# knobhead.net
KiCad netlist of a schematic drawn in EAGLE
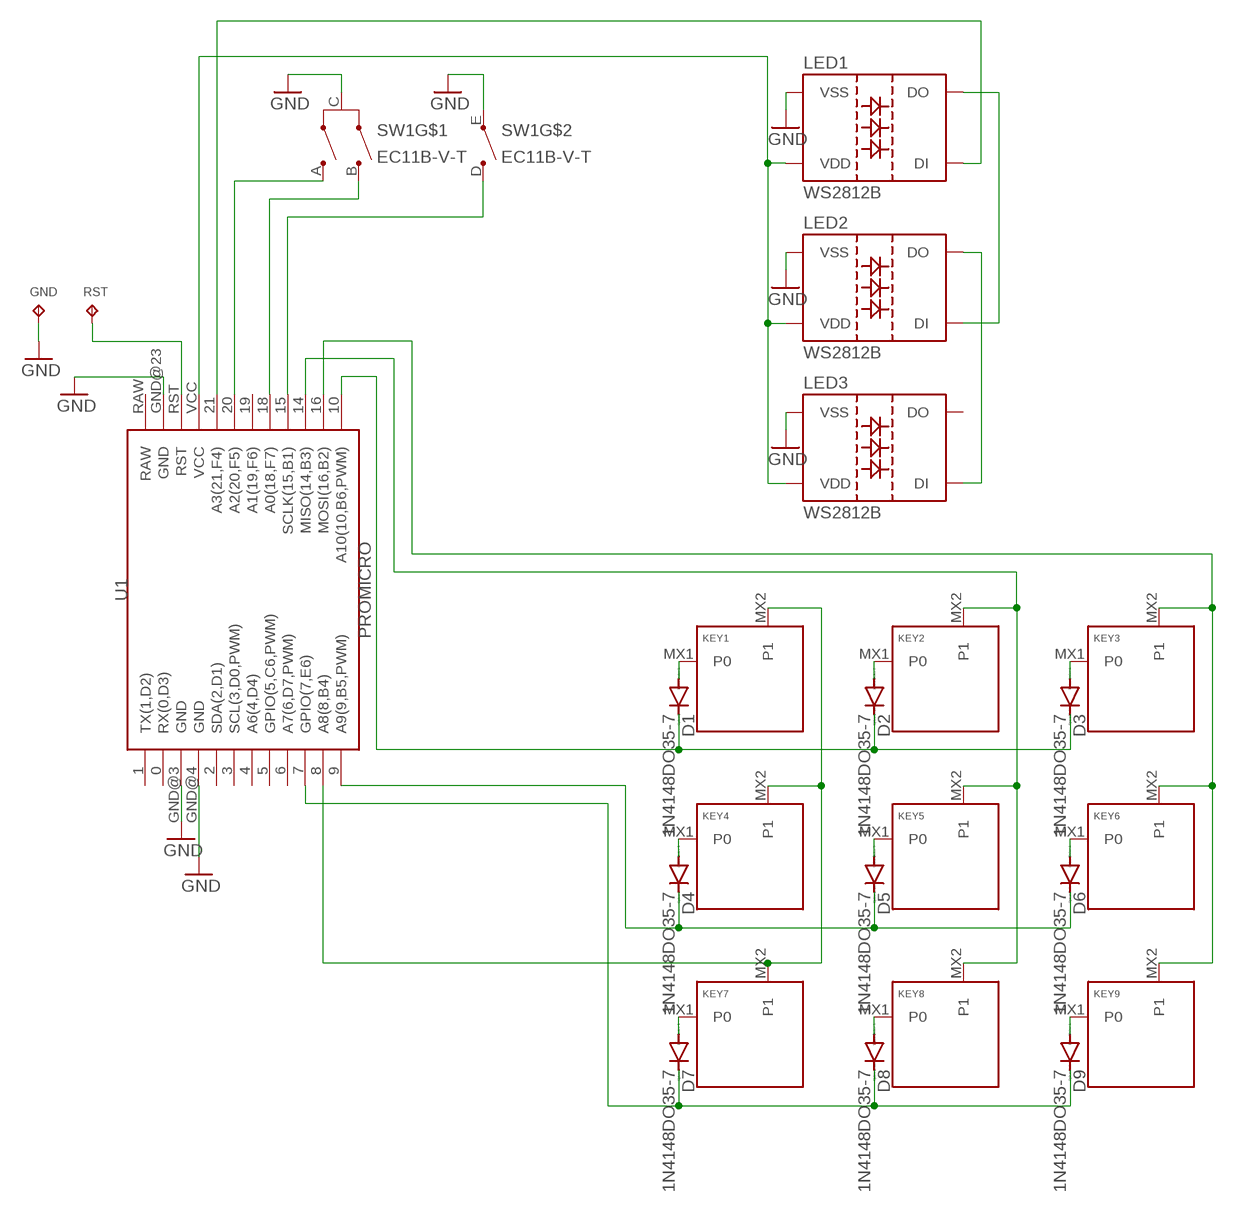
[diagram p0: schematic, sheet 1]

(export (version "E")
  (design (tool "Eeschema 10.0.6"))
  (components
    (comp (ref "D1")
      (value "1N4148DO35-7")
      (footprint "eagle-import:DO35-7")
      (libsource (lib "eagle-import") (part "1N4148DO35-7"))
    )
    (comp (ref "D2")
      (value "1N4148DO35-7")
      (footprint "eagle-import:DO35-7")
      (libsource (lib "eagle-import") (part "1N4148DO35-7"))
    )
    (comp (ref "D3")
      (value "1N4148DO35-7")
      (footprint "eagle-import:DO35-7")
      (libsource (lib "eagle-import") (part "1N4148DO35-7"))
    )
    (comp (ref "D4")
      (value "1N4148DO35-7")
      (footprint "eagle-import:DO35-7")
      (libsource (lib "eagle-import") (part "1N4148DO35-7"))
    )
    (comp (ref "D5")
      (value "1N4148DO35-7")
      (footprint "eagle-import:DO35-7")
      (libsource (lib "eagle-import") (part "1N4148DO35-7"))
    )
    (comp (ref "D6")
      (value "1N4148DO35-7")
      (footprint "eagle-import:DO35-7")
      (libsource (lib "eagle-import") (part "1N4148DO35-7"))
    )
    (comp (ref "D7")
      (value "1N4148DO35-7")
      (footprint "eagle-import:DO35-7")
      (libsource (lib "eagle-import") (part "1N4148DO35-7"))
    )
    (comp (ref "D8")
      (value "1N4148DO35-7")
      (footprint "eagle-import:DO35-7")
      (libsource (lib "eagle-import") (part "1N4148DO35-7"))
    )
    (comp (ref "D9")
      (value "1N4148DO35-7")
      (footprint "eagle-import:DO35-7")
      (libsource (lib "eagle-import") (part "1N4148DO35-7"))
    )
    (comp (ref "GND")
      (value "TPB1,27")
      (footprint "eagle-import:B1,27")
      (libsource (lib "eagle-import") (part "TPB1,27"))
    )
    (comp (ref "KEY1")
      (value "KEYSWITCH-PLAIN-MXHSPCB-1U")
      (footprint "eagle-import:MXHSPCB-1U")
      (libsource (lib "eagle-import") (part "KEYSWITCH-PLAIN-MXHSPCB-1U"))
    )
    (comp (ref "KEY2")
      (value "KEYSWITCH-PLAIN-MXHSPCB-1U")
      (footprint "eagle-import:MXHSPCB-1U")
      (libsource (lib "eagle-import") (part "KEYSWITCH-PLAIN-MXHSPCB-1U"))
    )
    (comp (ref "KEY3")
      (value "KEYSWITCH-PLAIN-MXHSPCB-1U")
      (footprint "eagle-import:MXHSPCB-1U")
      (libsource (lib "eagle-import") (part "KEYSWITCH-PLAIN-MXHSPCB-1U"))
    )
    (comp (ref "KEY4")
      (value "KEYSWITCH-PLAIN-MXHSPCB-1U")
      (footprint "eagle-import:MXHSPCB-1U")
      (libsource (lib "eagle-import") (part "KEYSWITCH-PLAIN-MXHSPCB-1U"))
    )
    (comp (ref "KEY5")
      (value "KEYSWITCH-PLAIN-MXHSPCB-1U")
      (footprint "eagle-import:MXHSPCB-1U")
      (libsource (lib "eagle-import") (part "KEYSWITCH-PLAIN-MXHSPCB-1U"))
    )
    (comp (ref "KEY6")
      (value "KEYSWITCH-PLAIN-MXHSPCB-1U")
      (footprint "eagle-import:MXHSPCB-1U")
      (libsource (lib "eagle-import") (part "KEYSWITCH-PLAIN-MXHSPCB-1U"))
    )
    (comp (ref "KEY7")
      (value "KEYSWITCH-PLAIN-MXHSPCB-1U")
      (footprint "eagle-import:MXHSPCB-1U")
      (libsource (lib "eagle-import") (part "KEYSWITCH-PLAIN-MXHSPCB-1U"))
    )
    (comp (ref "KEY8")
      (value "KEYSWITCH-PLAIN-MXHSPCB-1U")
      (footprint "eagle-import:MXHSPCB-1U")
      (libsource (lib "eagle-import") (part "KEYSWITCH-PLAIN-MXHSPCB-1U"))
    )
    (comp (ref "KEY9")
      (value "KEYSWITCH-PLAIN-MXHSPCB-1U")
      (footprint "eagle-import:MXHSPCB-1U")
      (libsource (lib "eagle-import") (part "KEYSWITCH-PLAIN-MXHSPCB-1U"))
    )
    (comp (ref "LED1")
      (value "WS2812B")
      (footprint "eagle-import:WS2812B")
      (libsource (lib "eagle-import") (part "WS2812B"))
    )
    (comp (ref "LED2")
      (value "WS2812B")
      (footprint "eagle-import:WS2812B")
      (libsource (lib "eagle-import") (part "WS2812B"))
    )
    (comp (ref "LED3")
      (value "WS2812B")
      (footprint "eagle-import:WS2812B")
      (libsource (lib "eagle-import") (part "WS2812B"))
    )
    (comp (ref "RST")
      (value "TPB1,27")
      (footprint "eagle-import:B1,27")
      (libsource (lib "eagle-import") (part "TPB1,27"))
    )
    (comp (ref "SW1")
      (value "EC11B-V-T")
      (footprint "eagle-import:EC11B-V")
      (libsource (lib "eagle-import") (part "EC11B-V-T"))
    )
    (comp (ref "U1")
      (value "PROMICRO")
      (footprint "eagle-import:PROMICRO")
      (libsource (lib "eagle-import") (part "PROMICRO"))
    )
  )
  (nets
    (net (code "1") (name "GND") (class "Default")
      (node (ref "GND") (pin "TP") (pinfunction "TP_TP") (pintype "input"))
      (node (ref "LED1") (pin "3") (pinfunction "VSS_3") (pintype "bidirectional"))
      (node (ref "LED2") (pin "3") (pinfunction "VSS_3") (pintype "bidirectional"))
      (node (ref "LED3") (pin "3") (pinfunction "VSS_3") (pintype "bidirectional"))
      (node (ref "SW1") (pin "C") (pinfunction "C_C") (pintype "passive"))
      (node (ref "SW1") (pin "E") (pinfunction "E_E") (pintype "passive"))
      (node (ref "U1") (pin "GND@23") (pinfunction "GND_GND@23") (pintype "bidirectional"))
      (node (ref "U1") (pin "GND@3") (pinfunction "GND_GND@3") (pintype "bidirectional"))
      (node (ref "U1") (pin "GND@4") (pinfunction "GND_GND@4") (pintype "bidirectional"))
    )
    (net (code "2") (name "Net-(KEY1-P0)") (class "Default")
      (node (ref "D1") (pin "A") (pinfunction "A_A") (pintype "passive"))
      (node (ref "KEY1") (pin "MX1") (pinfunction "P0_MX1") (pintype "bidirectional"))
    )
    (net (code "3") (name "Net-(KEY1-P1)") (class "Default")
      (node (ref "KEY1") (pin "MX2") (pinfunction "P1_MX2") (pintype "bidirectional"))
      (node (ref "KEY4") (pin "MX2") (pinfunction "P1_MX2") (pintype "bidirectional"))
      (node (ref "KEY7") (pin "MX2") (pinfunction "P1_MX2") (pintype "bidirectional"))
      (node (ref "U1") (pin "8") (pinfunction "A8(8,B4)_8") (pintype "bidirectional"))
    )
    (net (code "4") (name "Net-(KEY2-P0)") (class "Default")
      (node (ref "D2") (pin "A") (pinfunction "A_A") (pintype "passive"))
      (node (ref "KEY2") (pin "MX1") (pinfunction "P0_MX1") (pintype "bidirectional"))
    )
    (net (code "5") (name "Net-(KEY2-P1)") (class "Default")
      (node (ref "KEY2") (pin "MX2") (pinfunction "P1_MX2") (pintype "bidirectional"))
      (node (ref "KEY5") (pin "MX2") (pinfunction "P1_MX2") (pintype "bidirectional"))
      (node (ref "KEY8") (pin "MX2") (pinfunction "P1_MX2") (pintype "bidirectional"))
      (node (ref "U1") (pin "14") (pinfunction "MISO(14,B3)_14") (pintype "bidirectional"))
    )
    (net (code "6") (name "Net-(KEY3-P0)") (class "Default")
      (node (ref "D3") (pin "A") (pinfunction "A_A") (pintype "passive"))
      (node (ref "KEY3") (pin "MX1") (pinfunction "P0_MX1") (pintype "bidirectional"))
    )
    (net (code "7") (name "Net-(KEY3-P1)") (class "Default")
      (node (ref "KEY3") (pin "MX2") (pinfunction "P1_MX2") (pintype "bidirectional"))
      (node (ref "KEY6") (pin "MX2") (pinfunction "P1_MX2") (pintype "bidirectional"))
      (node (ref "KEY9") (pin "MX2") (pinfunction "P1_MX2") (pintype "bidirectional"))
      (node (ref "U1") (pin "16") (pinfunction "MOSI(16,B2)_16") (pintype "bidirectional"))
    )
    (net (code "8") (name "Net-(KEY4-P0)") (class "Default")
      (node (ref "D4") (pin "A") (pinfunction "A_A") (pintype "passive"))
      (node (ref "KEY4") (pin "MX1") (pinfunction "P0_MX1") (pintype "bidirectional"))
    )
    (net (code "9") (name "Net-(KEY5-P0)") (class "Default")
      (node (ref "D5") (pin "A") (pinfunction "A_A") (pintype "passive"))
      (node (ref "KEY5") (pin "MX1") (pinfunction "P0_MX1") (pintype "bidirectional"))
    )
    (net (code "10") (name "Net-(KEY6-P0)") (class "Default")
      (node (ref "D6") (pin "A") (pinfunction "A_A") (pintype "passive"))
      (node (ref "KEY6") (pin "MX1") (pinfunction "P0_MX1") (pintype "bidirectional"))
    )
    (net (code "11") (name "Net-(KEY7-P0)") (class "Default")
      (node (ref "D7") (pin "A") (pinfunction "A_A") (pintype "passive"))
      (node (ref "KEY7") (pin "MX1") (pinfunction "P0_MX1") (pintype "bidirectional"))
    )
    (net (code "12") (name "Net-(KEY8-P0)") (class "Default")
      (node (ref "D8") (pin "A") (pinfunction "A_A") (pintype "passive"))
      (node (ref "KEY8") (pin "MX1") (pinfunction "P0_MX1") (pintype "bidirectional"))
    )
    (net (code "13") (name "Net-(KEY9-P0)") (class "Default")
      (node (ref "D9") (pin "A") (pinfunction "A_A") (pintype "passive"))
      (node (ref "KEY9") (pin "MX1") (pinfunction "P0_MX1") (pintype "bidirectional"))
    )
    (net (code "14") (name "Net-(LED1-DI)") (class "Default")
      (node (ref "LED1") (pin "4") (pinfunction "DI_4") (pintype "bidirectional"))
      (node (ref "U1") (pin "21") (pinfunction "A3(21,F4)_21") (pintype "bidirectional"))
    )
    (net (code "15") (name "Net-(LED1-DO)") (class "Default")
      (node (ref "LED1") (pin "2") (pinfunction "DO_2") (pintype "bidirectional"))
      (node (ref "LED2") (pin "4") (pinfunction "DI_4") (pintype "bidirectional"))
    )
    (net (code "16") (name "Net-(LED1-VDD)") (class "Default")
      (node (ref "LED1") (pin "1") (pinfunction "VDD_1") (pintype "bidirectional"))
      (node (ref "LED2") (pin "1") (pinfunction "VDD_1") (pintype "bidirectional"))
      (node (ref "LED3") (pin "1") (pinfunction "VDD_1") (pintype "bidirectional"))
      (node (ref "U1") (pin "VCC") (pinfunction "VCC_VCC") (pintype "bidirectional"))
    )
    (net (code "17") (name "Net-(LED2-DO)") (class "Default")
      (node (ref "LED2") (pin "2") (pinfunction "DO_2") (pintype "bidirectional"))
      (node (ref "LED3") (pin "4") (pinfunction "DI_4") (pintype "bidirectional"))
    )
    (net (code "18") (name "Net-(RST-PadTP)") (class "Default")
      (node (ref "RST") (pin "TP") (pinfunction "TP_TP") (pintype "input"))
      (node (ref "U1") (pin "RST") (pinfunction "RST_RST") (pintype "bidirectional"))
    )
    (net (code "19") (name "Net-(U1-A0(18,F7))") (class "Default")
      (node (ref "SW1") (pin "B") (pinfunction "B_B") (pintype "passive"))
      (node (ref "U1") (pin "18") (pinfunction "A0(18,F7)_18") (pintype "bidirectional"))
    )
    (net (code "20") (name "Net-(U1-A2(20,F5))") (class "Default")
      (node (ref "SW1") (pin "A") (pinfunction "A_A") (pintype "passive"))
      (node (ref "U1") (pin "20") (pinfunction "A2(20,F5)_20") (pintype "bidirectional"))
    )
    (net (code "21") (name "Net-(U1-A9(9,B5,PWM))") (class "Default")
      (node (ref "D4") (pin "C") (pinfunction "C_C") (pintype "passive"))
      (node (ref "D5") (pin "C") (pinfunction "C_C") (pintype "passive"))
      (node (ref "D6") (pin "C") (pinfunction "C_C") (pintype "passive"))
      (node (ref "U1") (pin "9") (pinfunction "A9(9,B5,PWM)_9") (pintype "bidirectional"))
    )
    (net (code "22") (name "Net-(U1-A10(10,B6,PWM))") (class "Default")
      (node (ref "D1") (pin "C") (pinfunction "C_C") (pintype "passive"))
      (node (ref "D2") (pin "C") (pinfunction "C_C") (pintype "passive"))
      (node (ref "D3") (pin "C") (pinfunction "C_C") (pintype "passive"))
      (node (ref "U1") (pin "10") (pinfunction "A10(10,B6,PWM)_10") (pintype "bidirectional"))
    )
    (net (code "23") (name "Net-(U1-GPIO(7,E6))") (class "Default")
      (node (ref "D7") (pin "C") (pinfunction "C_C") (pintype "passive"))
      (node (ref "D8") (pin "C") (pinfunction "C_C") (pintype "passive"))
      (node (ref "D9") (pin "C") (pinfunction "C_C") (pintype "passive"))
      (node (ref "U1") (pin "7") (pinfunction "GPIO(7,E6)_7") (pintype "bidirectional"))
    )
    (net (code "24") (name "Net-(U1-SCLK(15,B1))") (class "Default")
      (node (ref "SW1") (pin "D") (pinfunction "D_D") (pintype "passive"))
      (node (ref "U1") (pin "15") (pinfunction "SCLK(15,B1)_15") (pintype "bidirectional"))
    )
    (net (code "25") (name "unconnected-(LED3-DO-Pad2)") (class "Default")
      (node (ref "LED3") (pin "2") (pinfunction "DO_2") (pintype "bidirectional"))
    )
    (net (code "26") (name "unconnected-(U1-A1(19,F6)-Pad19)") (class "Default")
      (node (ref "U1") (pin "19") (pinfunction "A1(19,F6)_19") (pintype "bidirectional"))
    )
    (net (code "27") (name "unconnected-(U1-A6(4,D4)-Pad4)") (class "Default")
      (node (ref "U1") (pin "4") (pinfunction "A6(4,D4)_4") (pintype "bidirectional"))
    )
    (net (code "28") (name "unconnected-(U1-A7(6,D7,PWM)-Pad6)") (class "Default")
      (node (ref "U1") (pin "6") (pinfunction "A7(6,D7,PWM)_6") (pintype "bidirectional"))
    )
    (net (code "29") (name "unconnected-(U1-GPIO(5,C6,PWM)-Pad5)") (class "Default")
      (node (ref "U1") (pin "5") (pinfunction "GPIO(5,C6,PWM)_5") (pintype "bidirectional"))
    )
    (net (code "30") (name "unconnected-(U1-PadRAW)") (class "Default")
      (node (ref "U1") (pin "RAW") (pinfunction "RAW_RAW") (pintype "bidirectional"))
    )
    (net (code "31") (name "unconnected-(U1-RX(0,D3)-Pad0)") (class "Default")
      (node (ref "U1") (pin "0") (pinfunction "RX(0,D3)_0") (pintype "bidirectional"))
    )
    (net (code "32") (name "unconnected-(U1-SCL(3,D0,PWM)-Pad3)") (class "Default")
      (node (ref "U1") (pin "3") (pinfunction "SCL(3,D0,PWM)_3") (pintype "bidirectional"))
    )
    (net (code "33") (name "unconnected-(U1-SDA(2,D1)-Pad2)") (class "Default")
      (node (ref "U1") (pin "2") (pinfunction "SDA(2,D1)_2") (pintype "bidirectional"))
    )
    (net (code "34") (name "unconnected-(U1-TX(1,D2)-Pad1)") (class "Default")
      (node (ref "U1") (pin "1") (pinfunction "TX(1,D2)_1") (pintype "bidirectional"))
    )
  )
)
